# RF_Board_with_STM32.net
KiCad netlist of a schematic drawn in Altium Designer
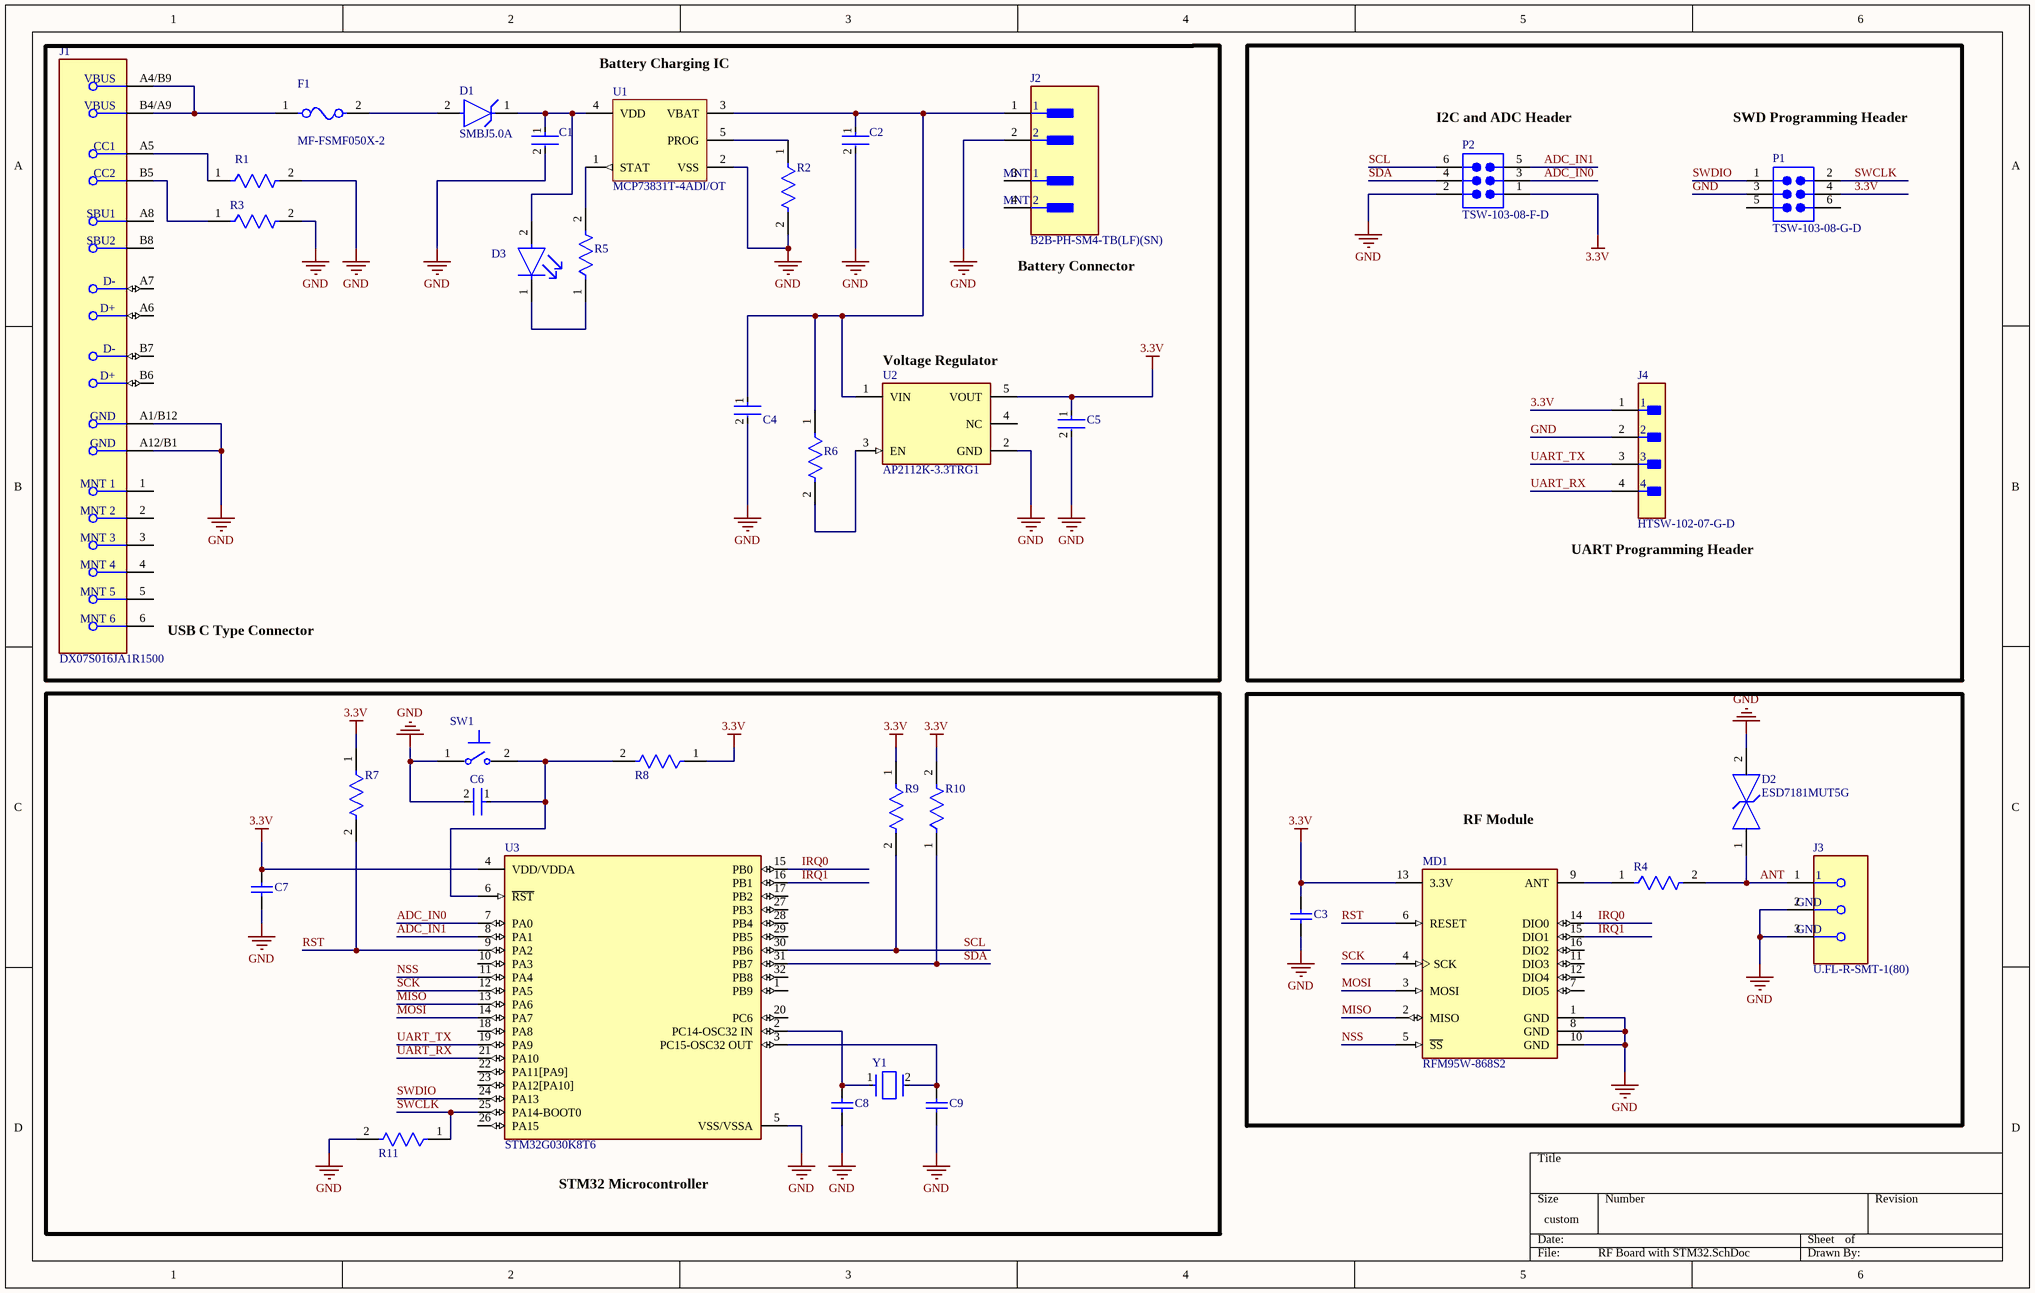
[diagram p0: RF Board with STM32.SchDoc]

(export (version "E")
  (design (tool "Eeschema 10.0.6"))
  (components
    (comp (ref "C1")
      (value "GRM188R61E475KE11J")
      (footprint "FP-GRM188-0_15-IPC_A")
      (description "Chip Multilayer Ceramic Capacitors for General Purpose, 0603, 4.7uF, X5R, 15%, 10%, 25V")
      (fields (field (name "TOLERANCE") "10%"))
      (libsource (lib "Altium Content Vault") (part "02cd4be3c70576c341d710602a673aa"))
    )
    (comp (ref "C2")
      (value "GRM188R61E475KE11J")
      (footprint "FP-GRM188-0_15-IPC_A")
      (description "Chip Multilayer Ceramic Capacitors for General Purpose, 0603, 4.7uF, X5R, 15%, 10%, 25V")
      (fields (field (name "TOLERANCE") "10%"))
      (libsource (lib "Altium Content Vault") (part "02cd4be3c70576c341d710602a673aa"))
    )
    (comp (ref "C3")
      (value "06031A100CAT2A")
      (footprint "CAPC1608X90X35ML15T15")
      (fields (field (name "MANUFACTURER") "AVX Interconnect / Elco"))
      (libsource (lib "Altium Content Vault") (part "CAP"))
    )
    (comp (ref "C4")
      (value "GRM155C81A105KA12J")
      (footprint "FP-GRM155-0_05-IPC_A")
      (description "Chip Multilayer Ceramic Capacitors for General Purpose, 0402, 1.0uF, X6S, 22%, 10%, 10V")
      (fields (field (name "TOLERANCE") "10%"))
      (libsource (lib "Altium Content Vault") (part "02cd4be3c70576c341d710602a673aa"))
    )
    (comp (ref "C5")
      (value "GRM155C81A105KA12J")
      (footprint "FP-GRM155-0_05-IPC_A")
      (description "Chip Multilayer Ceramic Capacitors for General Purpose, 0402, 1.0uF, X6S, 22%, 10%, 10V")
      (fields (field (name "TOLERANCE") "10%"))
      (libsource (lib "Altium Content Vault") (part "02cd4be3c70576c341d710602a673aa"))
    )
    (comp (ref "C6")
      (value "GRM033R61A104KE15D")
      (footprint "FP-GRM033-0_03-IPC_C")
      (description "Chip Multilayer Ceramic Capacitors for General Purpose, 0201, 0.10uF, X5R, 15%, 10%, 10V")
      (fields (field (name "TOLERANCE") "10%") (field (name "VOLTAGE") "10V"))
      (libsource (lib "Altium Content Vault") (part "b4654b650e69147ec39a6b967a45e02"))
    )
    (comp (ref "C7")
      (value "06031A100CAT2A")
      (footprint "CAPC1608X90X35ML15T15")
      (fields (field (name "MANUFACTURER") "AVX Interconnect / Elco"))
      (libsource (lib "Altium Content Vault") (part "CAP"))
    )
    (comp (ref "C8")
      (value "VJ0603Y104KXJAC")
      (footprint "CAPC1608X92X38NL15T08")
      (fields (field (name "MANUFACTURER") "Vitramon"))
      (libsource (lib "Altium Content Vault") (part "CAP"))
    )
    (comp (ref "C9")
      (value "VJ0603Y104KXJAC")
      (footprint "CAPC1608X92X38NL15T08")
      (fields (field (name "MANUFACTURER") "Vitramon"))
      (libsource (lib "Altium Content Vault") (part "CAP"))
    )
    (comp (ref "D1")
      (value "SMBJ5.0A")
      (footprint "FP-SMBJ-MFG")
      (description "TVS DIODE 5V 9.2V SMB")
      (fields
        (field (name "OCTOPART") "https://octopart.com/smbj5.0a-bourns-12809487")
        (field (name "MANUFACTURER") "Bourns Inc.")
      )
      (libsource (lib "Altium Content Vault") (part "f813f71cba58e380607f5dd3caf9714"))
    )
    (comp (ref "D2")
      (value "ESD7181MUT5G")
      (footprint "FP-152AF-MFG")
      (description "ESD7181MUT5G ESD Suppressor Diode TVS Bi-Dir 18.5V 2-Pin X3-DFN T/R / TVS DIODE 18.5VWM 35VC")
      (libsource (lib "Altium Content Vault") (part "11bd9d59d340f0612179daf16ad9b72"))
    )
    (comp (ref "D3")
      (value "LS R976-NR-1")
      (footprint "FP-LS_R976-MFG")
      (description "LED RED DIFFUSED 0805 SMD")
      (libsource (lib "Altium Content Vault") (part "8706943c75ba83719d021d2fdc84c58"))
    )
    (comp (ref "F1")
      (value "MF-FSMF050X-2")
      (footprint "FP-MF-FSMF-MFG")
      (description "PTC RESET FUSE 6V 500MA 0603")
      (fields
        (field (name "MANUFACTURER") "Bourns Inc.")
        (field (name "OCTOPART") "https://octopart.com/mf-fsmf050x-2-bourns-10470804")
      )
      (libsource (lib "Altium Content Vault") (part "5bcf9b9f640e542cf0359d10258e979"))
    )
    (comp (ref "J1")
      (value "DX07S016JA1R1500")
      (footprint "FP-DX07S016JA1R1500-MFG")
      (description "CONN RCP USB2.0 TYP C 24P SMD RA")
      (libsource (lib "Altium Content Vault") (part "7f3e9989102a0f22bff9cb010881d34"))
    )
    (comp (ref "J2")
      (value "B2B-PH-SM4-TB(LF)(SN)")
      (footprint "FP-B2B-PH-SM4-TB_LF_SN-MFG")
      (description "CONN HEADER SMD 2POS 2MM")
      (libsource (lib "Altium Content Vault") (part "56ec3178a87b3978bdc1b3682cd516a"))
    )
    (comp (ref "J3")
      (value "U.FL-R-SMT-1(80)")
      (footprint "FP-U_FL-R-SMT-1_80-MFG")
      (description "CONN U.FL RCPT STR 50 OHM SMD")
      (libsource (lib "Altium Content Vault") (part "ad010367dc7cd7c7a13299a56582dd6"))
    )
    (comp (ref "J4")
      (value "HTSW-102-07-G-D")
      (footprint "FP-HTSW-102-07-G-D-MFG")
      (description "CONN HEADER VERT 4POS 2.54MM")
      (fields
        (field (name "MANUFACTURER") "Samtec")
        (field (name "OCTOPART") "https://octopart.com/htsw-102-07-g-d-samtec-10531767")
      )
      (libsource (lib "Altium Content Vault") (part "299a8cea1bdcbc3624fe62c390fa72c"))
    )
    (comp (ref "MD1")
      (value "RFM95W-868S2")
      (footprint "FP-RFM95W-868S2-MFG")
      (description "RX TXRX MODULE ISM < 1GHZ SMD")
      (libsource (lib "Altium Content Vault") (part "17626aa6fba47fab2b206b7c140802e"))
    )
    (comp (ref "P1")
      (value "TSW-103-08-G-D")
      (footprint "SMTC-TSW-103-08-X-D")
      (description "0.025\" SQ Post Header, Through-hole, Vertical, -55 to 125 degC, 2.54 mm Pitch, 6-Pin, Male, RoHS")
      (fields (field (name "MANUFACTURER") "Samtec"))
      (libsource (lib "Altium Content Vault") (part "SMTC-TSW-103-08-X-D"))
    )
    (comp (ref "P2")
      (value "TSW-103-08-F-D")
      (footprint "SMTC-TSW-103-08-X-D")
      (description "0.025\" SQ Post Header, Through-hole, Vertical, -55 to 125 degC, 2.54 mm Pitch, 6-Pin, Male, RoHS")
      (fields (field (name "MANUFACTURER") "Samtec"))
      (libsource (lib "Altium Content Vault") (part "SMTC-TSW-103-08-X-D"))
    )
    (comp (ref "R1")
      (value "AC0603FR-075K1L")
      (footprint "FP-AC0603-MFG")
      (description "RES 5.1KΩ 1.00% 0.1W 0603")
      (fields (field (name "TOLERANCE") "1%"))
      (libsource (lib "Altium Content Vault") (part "1029c3af85768c4190bb7ad29bc67b5"))
    )
    (comp (ref "R2")
      (value "RP73PF1J2K0BTDF")
      (footprint "FP-RP73P-1J-MFG")
      (description "RES SMD 2K OHM 0.1% 1/6W 0603")
      (fields (field (name "TOLERANCE") "0.001") (field (name "MANUFACTURER") "TE Connectivity"))
      (libsource (lib "Altium Content Vault") (part "1029c3af85768c4190bb7ad29bc67b5"))
    )
    (comp (ref "R3")
      (value "AC0603FR-075K1L")
      (footprint "FP-AC0603-MFG")
      (description "RES 5.1KΩ 1.00% 0.1W 0603")
      (fields (field (name "TOLERANCE") "1%"))
      (libsource (lib "Altium Content Vault") (part "1029c3af85768c4190bb7ad29bc67b5"))
    )
    (comp (ref "R4")
      (value "CRG0603ZR")
      (footprint "FP-CRG0603-IPC_C")
      (description "RES SMD 0 OHM JUMPER 1/10W 0603")
      (fields (field (name "TOLERANCE") "0%"))
      (libsource (lib "Altium Content Vault") (part "1029c3af85768c4190bb7ad29bc67b5"))
    )
    (comp (ref "R5")
      (value "RT0603BRD07470RL")
      (footprint "FP-RT0603-MFG")
      (description "RES SMD 470 OHM 0.1% 1/10W 0603")
      (fields
        (field (name "OCTOPART") "https://octopart.com/rt0603brd07470rl-yageo-1424253")
        (field (name "MANUFACTURER") "Yageo")
      )
      (libsource (lib "Altium Content Vault") (part "1029c3af85768c4190bb7ad29bc67b5"))
    )
    (comp (ref "R6")
      (value "ERJ-U02F1003X")
      (footprint "FP-ERJU02-MFG")
      (fields (field (name "TOLERANCE") "1%"))
      (libsource (lib "Altium Content Vault") (part "1029c3af85768c4190bb7ad29bc67b5"))
    )
    (comp (ref "R7")
      (value "RT0603FRE1010KL")
      (footprint "FP-RT0603-MFG")
      (description "RT0603 10KΩ 0.1W 50 ppm/°C 1.00%")
      (fields
        (field (name "OCTOPART") "https://octopart.com/rt0603fre1010kl-yageo-26185585")
        (field (name "TOLERANCE") "0.01")
      )
      (libsource (lib "Altium Content Vault") (part "1029c3af85768c4190bb7ad29bc67b5"))
    )
    (comp (ref "R8")
      (value "RT0603FRE1010KL")
      (footprint "FP-RT0603-MFG")
      (description "RT0603 10KΩ 0.1W 50 ppm/°C 1.00%")
      (fields
        (field (name "OCTOPART") "https://octopart.com/rt0603fre1010kl-yageo-26185585")
        (field (name "TOLERANCE") "0.01")
      )
      (libsource (lib "Altium Content Vault") (part "1029c3af85768c4190bb7ad29bc67b5"))
    )
    (comp (ref "R9")
      (value "CRG0402F4K7")
      (footprint "FP-CRG0402-IPC_B")
      (description "RES SMD 4.7K OHM 1% 1/16W 0402")
      (libsource (lib "Altium Content Vault") (part "1029c3af85768c4190bb7ad29bc67b5"))
    )
    (comp (ref "R10")
      (value "CRG0402F4K7")
      (footprint "FP-CRG0402-IPC_B")
      (description "RES SMD 4.7K OHM 1% 1/16W 0402")
      (libsource (lib "Altium Content Vault") (part "1029c3af85768c4190bb7ad29bc67b5"))
    )
    (comp (ref "R11")
      (value "RT0603FRE1010KL")
      (footprint "FP-RT0603-MFG")
      (description "RT0603 10KΩ 0.1W 50 ppm/°C 1.00%")
      (fields
        (field (name "OCTOPART") "https://octopart.com/rt0603fre1010kl-yageo-26185585")
        (field (name "TOLERANCE") "0.01")
      )
      (libsource (lib "Altium Content Vault") (part "1029c3af85768c4190bb7ad29bc67b5"))
    )
    (comp (ref "SW1")
      (value "TL1015AF160QG")
      (footprint "FP-TL1015AF160QG-MFG")
      (description "SWITCH TACTILE SPST-NO 0.05A 12V")
      (libsource (lib "Altium Content Vault") (part "2041f8efb62e6aaa548c9fd35e2c2f1"))
    )
    (comp (ref "U1")
      (value "MCP73831T-4ADI/OT")
      (footprint "SOT-23-OT5_N")
      (libsource (lib "Altium Content Vault") (part "PM-BM-MCP73831-SOT5"))
    )
    (comp (ref "U2")
      (value "AP2112K-3.3TRG1")
      (footprint "FP-SOT25-IPC_A")
      (description "IC REG LINEAR 3.3V 600MA SOT25")
      (libsource (lib "Altium Content Vault") (part "c8ab751aee5229183125ab046a11caa"))
    )
    (comp (ref "U3")
      (value "STM32G030K8T6")
      (footprint "FP-LQFP32-5V-IPC_A")
      (description "IC MCU 32BIT 64KB FLASH 32LQFP")
      (libsource (lib "Altium Content Vault") (part "fea91388a178aa646681c81fcef9c35"))
    )
    (comp (ref "Y1")
      (value "ABS07-32.768KHZ-7-T")
      (footprint "FP-ABS07-MFG")
      (description "Crystal 32.768kHz ±20ppm (Tol) 7pF FUND 70kΩ 2-Pin CSMD T/R")
      (fields (field (name "TOLERANCE") "20ppm"))
      (libsource (lib "Altium Content Vault") (part "c23a69dc6c9e2f18f2079038eb95dd1"))
    )
  )
  (nets
    (net (code "2") (name "/ADC_IN0") (class "Default")
      (node (ref "P2") (pin "3") (pinfunction "3_3") (pintype "passive"))
      (node (ref "U3") (pin "7") (pinfunction "PA0_7") (pintype "bidirectional"))
    )
    (net (code "3") (name "/ADC_IN1") (class "Default")
      (node (ref "P2") (pin "5") (pinfunction "5_5") (pintype "passive"))
      (node (ref "U3") (pin "8") (pinfunction "PA1_8") (pintype "bidirectional"))
    )
    (net (code "4") (name "/ANT") (class "Default")
      (node (ref "D2") (pin "1") (pinfunction "1_1") (pintype "passive"))
      (node (ref "J3") (pin "1") (pinfunction "1_1") (pintype "passive"))
      (node (ref "R4") (pin "2") (pinfunction "2_2") (pintype "passive"))
    )
    (net (code "5") (name "/IRQ0") (class "Default")
      (node (ref "MD1") (pin "14") (pinfunction "DIO0_14") (pintype "bidirectional"))
      (node (ref "U3") (pin "15") (pinfunction "PB0_15") (pintype "bidirectional"))
    )
    (net (code "6") (name "/IRQ1") (class "Default")
      (node (ref "MD1") (pin "15") (pinfunction "DIO1_15") (pintype "bidirectional"))
      (node (ref "U3") (pin "16") (pinfunction "PB1_16") (pintype "bidirectional"))
    )
    (net (code "7") (name "/MISO") (class "Default")
      (node (ref "MD1") (pin "2") (pinfunction "MISO_2") (pintype "bidirectional"))
      (node (ref "U3") (pin "13") (pinfunction "PA6_13") (pintype "bidirectional"))
    )
    (net (code "8") (name "/MOSI") (class "Default")
      (node (ref "MD1") (pin "3") (pinfunction "MOSI_3") (pintype "input"))
      (node (ref "U3") (pin "14") (pinfunction "PA7_14") (pintype "bidirectional"))
    )
    (net (code "9") (name "/NSS") (class "Default")
      (node (ref "MD1") (pin "5") (pinfunction "~{SS}_5") (pintype "input"))
      (node (ref "U3") (pin "11") (pinfunction "PA4_11") (pintype "bidirectional"))
    )
    (net (code "10") (name "/RST") (class "Default")
      (node (ref "MD1") (pin "6") (pinfunction "RESET_6") (pintype "input"))
      (node (ref "R7") (pin "2") (pinfunction "2_2") (pintype "passive"))
      (node (ref "U3") (pin "9") (pinfunction "PA2_9") (pintype "bidirectional"))
    )
    (net (code "11") (name "/SCK") (class "Default")
      (node (ref "MD1") (pin "4") (pinfunction "SCK_4") (pintype "input"))
      (node (ref "U3") (pin "12") (pinfunction "PA5_12") (pintype "bidirectional"))
    )
    (net (code "12") (name "/SCL") (class "Default")
      (node (ref "P2") (pin "6") (pinfunction "6_6") (pintype "passive"))
      (node (ref "R9") (pin "2") (pinfunction "2_2") (pintype "passive"))
      (node (ref "U3") (pin "30") (pinfunction "PB6_30") (pintype "bidirectional"))
    )
    (net (code "13") (name "/SDA") (class "Default")
      (node (ref "P2") (pin "4") (pinfunction "4_4") (pintype "passive"))
      (node (ref "R10") (pin "1") (pinfunction "1_1") (pintype "passive"))
      (node (ref "U3") (pin "31") (pinfunction "PB7_31") (pintype "bidirectional"))
    )
    (net (code "14") (name "/SWCLK") (class "Default")
      (node (ref "P1") (pin "2") (pinfunction "2_2") (pintype "passive"))
      (node (ref "R11") (pin "1") (pinfunction "1_1") (pintype "passive"))
      (node (ref "U3") (pin "25") (pinfunction "PA14-BOOT0_25") (pintype "bidirectional"))
    )
    (net (code "15") (name "/SWDIO") (class "Default")
      (node (ref "P1") (pin "1") (pinfunction "1_1") (pintype "passive"))
      (node (ref "U3") (pin "24") (pinfunction "PA13_24") (pintype "bidirectional"))
    )
    (net (code "16") (name "/UART_RX") (class "Default")
      (node (ref "J4") (pin "4") (pinfunction "4_4") (pintype "passive"))
      (node (ref "U3") (pin "21") (pinfunction "PA10_21") (pintype "bidirectional"))
    )
    (net (code "17") (name "/UART_TX") (class "Default")
      (node (ref "J4") (pin "3") (pinfunction "3_3") (pintype "passive"))
      (node (ref "U3") (pin "19") (pinfunction "PA9_19") (pintype "bidirectional"))
    )
    (net (code "18") (name "3.3V") (class "Default")
      (node (ref "C3") (pin "2") (pinfunction "2_2") (pintype "passive"))
      (node (ref "C5") (pin "1") (pinfunction "1_1") (pintype "passive"))
      (node (ref "C7") (pin "2") (pinfunction "2_2") (pintype "passive"))
      (node (ref "J4") (pin "1") (pinfunction "1_1") (pintype "passive"))
      (node (ref "MD1") (pin "13") (pinfunction "3.3V_13") (pintype "power_in"))
      (node (ref "P1") (pin "4") (pinfunction "4_4") (pintype "passive"))
      (node (ref "P2") (pin "1") (pinfunction "1_1") (pintype "passive"))
      (node (ref "R10") (pin "2") (pinfunction "2_2") (pintype "passive"))
      (node (ref "R7") (pin "1") (pinfunction "1_1") (pintype "passive"))
      (node (ref "R8") (pin "1") (pinfunction "1_1") (pintype "passive"))
      (node (ref "R9") (pin "1") (pinfunction "1_1") (pintype "passive"))
      (node (ref "U2") (pin "5") (pinfunction "VOUT_5") (pintype "power_in"))
      (node (ref "U3") (pin "4") (pinfunction "VDD/VDDA_4") (pintype "power_in"))
    )
    (net (code "19") (name "GND") (class "Default")
      (node (ref "C1") (pin "2") (pinfunction "2_2") (pintype "passive"))
      (node (ref "C2") (pin "2") (pinfunction "2_2") (pintype "passive"))
      (node (ref "C3") (pin "1") (pinfunction "1_1") (pintype "passive"))
      (node (ref "C4") (pin "2") (pinfunction "2_2") (pintype "passive"))
      (node (ref "C5") (pin "2") (pinfunction "2_2") (pintype "passive"))
      (node (ref "C6") (pin "2") (pinfunction "2_2") (pintype "passive"))
      (node (ref "C7") (pin "1") (pinfunction "1_1") (pintype "passive"))
      (node (ref "C8") (pin "1") (pinfunction "1_1") (pintype "passive"))
      (node (ref "C9") (pin "1") (pinfunction "1_1") (pintype "passive"))
      (node (ref "D2") (pin "2") (pinfunction "2_2") (pintype "passive"))
      (node (ref "J1") (pin "A1/B12") (pinfunction "GND_A1/B12") (pintype "power_in"))
      (node (ref "J1") (pin "A12/B1") (pinfunction "GND_A12/B1") (pintype "power_in"))
      (node (ref "J2") (pin "2") (pinfunction "2_2") (pintype "passive"))
      (node (ref "J3") (pin "2") (pinfunction "GND_2") (pintype "power_in"))
      (node (ref "J3") (pin "3") (pinfunction "GND_3") (pintype "power_in"))
      (node (ref "J4") (pin "2") (pinfunction "2_2") (pintype "passive"))
      (node (ref "MD1") (pin "1") (pinfunction "GND_1") (pintype "power_in"))
      (node (ref "MD1") (pin "10") (pinfunction "GND_10") (pintype "power_in"))
      (node (ref "MD1") (pin "8") (pinfunction "GND_8") (pintype "power_in"))
      (node (ref "P1") (pin "3") (pinfunction "3_3") (pintype "passive"))
      (node (ref "P2") (pin "2") (pinfunction "2_2") (pintype "passive"))
      (node (ref "R1") (pin "2") (pinfunction "2_2") (pintype "passive"))
      (node (ref "R11") (pin "2") (pinfunction "2_2") (pintype "passive"))
      (node (ref "R2") (pin "2") (pinfunction "2_2") (pintype "passive"))
      (node (ref "R3") (pin "2") (pinfunction "2_2") (pintype "passive"))
      (node (ref "SW1") (pin "1") (pinfunction "1_1") (pintype "passive"))
      (node (ref "U1") (pin "2") (pinfunction "VSS_2") (pintype "power_in"))
      (node (ref "U2") (pin "2") (pinfunction "GND_2") (pintype "power_in"))
      (node (ref "U3") (pin "5") (pinfunction "VSS/VSSA_5") (pintype "power_in"))
    )
    (net (code "20") (name "Net-(D1-A)") (class "Default")
      (node (ref "D1") (pin "2") (pinfunction "A_2") (pintype "passive"))
      (node (ref "F1") (pin "2") (pinfunction "2_2") (pintype "passive"))
    )
    (net (code "21") (name "Net-(D1-C)") (class "Default")
      (node (ref "C1") (pin "1") (pinfunction "1_1") (pintype "passive"))
      (node (ref "D1") (pin "1") (pinfunction "C_1") (pintype "passive"))
      (node (ref "D3") (pin "2") (pinfunction "A_2") (pintype "passive"))
      (node (ref "U1") (pin "4") (pinfunction "VDD_4") (pintype "power_in"))
    )
    (net (code "22") (name "Net-(D3-C)") (class "Default")
      (node (ref "D3") (pin "1") (pinfunction "C_1") (pintype "passive"))
      (node (ref "R5") (pin "1") (pinfunction "1_1") (pintype "passive"))
    )
    (net (code "23") (name "Net-(F1-Pad1)") (class "Default")
      (node (ref "F1") (pin "1") (pinfunction "1_1") (pintype "passive"))
      (node (ref "J1") (pin "A4/B9") (pinfunction "VBUS_A4/B9") (pintype "power_in"))
      (node (ref "J1") (pin "B4/A9") (pinfunction "VBUS_B4/A9") (pintype "power_in"))
    )
    (net (code "24") (name "Net-(J1-CC1)") (class "Default")
      (node (ref "J1") (pin "A5") (pinfunction "CC1_A5") (pintype "passive"))
      (node (ref "R1") (pin "1") (pinfunction "1_1") (pintype "passive"))
    )
    (net (code "25") (name "Net-(J1-CC2)") (class "Default")
      (node (ref "J1") (pin "B5") (pinfunction "CC2_B5") (pintype "passive"))
      (node (ref "R3") (pin "1") (pinfunction "1_1") (pintype "passive"))
    )
    (net (code "26") (name "Net-(MD1-ANT)") (class "Default")
      (node (ref "MD1") (pin "9") (pinfunction "ANT_9") (pintype "passive"))
      (node (ref "R4") (pin "1") (pinfunction "1_1") (pintype "passive"))
    )
    (net (code "27") (name "Net-(U1-PROG)") (class "Default")
      (node (ref "R2") (pin "1") (pinfunction "1_1") (pintype "passive"))
      (node (ref "U1") (pin "5") (pinfunction "PROG_5") (pintype "passive"))
    )
    (net (code "28") (name "Net-(U1-STAT)") (class "Default")
      (node (ref "R5") (pin "2") (pinfunction "2_2") (pintype "passive"))
      (node (ref "U1") (pin "1") (pinfunction "STAT_1") (pintype "output"))
    )
    (net (code "29") (name "Net-(U1-VBAT)") (class "Default")
      (node (ref "C2") (pin "1") (pinfunction "1_1") (pintype "passive"))
      (node (ref "C4") (pin "1") (pinfunction "1_1") (pintype "passive"))
      (node (ref "J2") (pin "1") (pinfunction "1_1") (pintype "passive"))
      (node (ref "R6") (pin "1") (pinfunction "1_1") (pintype "passive"))
      (node (ref "U1") (pin "3") (pinfunction "VBAT_3") (pintype "power_in"))
      (node (ref "U2") (pin "1") (pinfunction "VIN_1") (pintype "power_in"))
    )
    (net (code "30") (name "Net-(U2-EN)") (class "Default")
      (node (ref "R6") (pin "2") (pinfunction "2_2") (pintype "passive"))
      (node (ref "U2") (pin "3") (pinfunction "EN_3") (pintype "input"))
    )
    (net (code "31") (name "Net-(U3-PC14-OSC32_IN)") (class "Default")
      (node (ref "C8") (pin "2") (pinfunction "2_2") (pintype "passive"))
      (node (ref "U3") (pin "2") (pinfunction "PC14-OSC32_IN_2") (pintype "bidirectional"))
      (node (ref "Y1") (pin "1") (pinfunction "1_1") (pintype "passive"))
    )
    (net (code "32") (name "Net-(U3-PC15-OSC32_OUT)") (class "Default")
      (node (ref "C9") (pin "2") (pinfunction "2_2") (pintype "passive"))
      (node (ref "U3") (pin "3") (pinfunction "PC15-OSC32_OUT_3") (pintype "bidirectional"))
      (node (ref "Y1") (pin "2") (pinfunction "2_2") (pintype "passive"))
    )
    (net (code "33") (name "Net-(U3-~{RST})") (class "Default")
      (node (ref "C6") (pin "1") (pinfunction "1_1") (pintype "passive"))
      (node (ref "R8") (pin "2") (pinfunction "2_2") (pintype "passive"))
      (node (ref "SW1") (pin "2") (pinfunction "2_2") (pintype "passive"))
      (node (ref "U3") (pin "6") (pinfunction "~{RST}_6") (pintype "input"))
    )
    (net (code "34") (name "unconnected-(J1-D+-PadA6)") (class "Default")
      (node (ref "J1") (pin "A6") (pinfunction "D+_A6") (pintype "bidirectional"))
    )
    (net (code "35") (name "unconnected-(J1-D+-PadB6)") (class "Default")
      (node (ref "J1") (pin "B6") (pinfunction "D+_B6") (pintype "bidirectional"))
    )
    (net (code "36") (name "unconnected-(J1-D--PadA7)") (class "Default")
      (node (ref "J1") (pin "A7") (pinfunction "D-_A7") (pintype "bidirectional"))
    )
    (net (code "37") (name "unconnected-(J1-D--PadB7)") (class "Default")
      (node (ref "J1") (pin "B7") (pinfunction "D-_B7") (pintype "bidirectional"))
    )
    (net (code "38") (name "unconnected-(J1-MNT_1-Pad1)") (class "Default")
      (node (ref "J1") (pin "1") (pinfunction "MNT_1_1") (pintype "passive"))
    )
    (net (code "39") (name "unconnected-(J1-MNT_2-Pad2)") (class "Default")
      (node (ref "J1") (pin "2") (pinfunction "MNT_2_2") (pintype "passive"))
    )
    (net (code "40") (name "unconnected-(J1-MNT_3-Pad3)") (class "Default")
      (node (ref "J1") (pin "3") (pinfunction "MNT_3_3") (pintype "passive"))
    )
    (net (code "41") (name "unconnected-(J1-MNT_4-Pad4)") (class "Default")
      (node (ref "J1") (pin "4") (pinfunction "MNT_4_4") (pintype "passive"))
    )
    (net (code "42") (name "unconnected-(J1-MNT_5-Pad5)") (class "Default")
      (node (ref "J1") (pin "5") (pinfunction "MNT_5_5") (pintype "passive"))
    )
    (net (code "43") (name "unconnected-(J1-MNT_6-Pad6)") (class "Default")
      (node (ref "J1") (pin "6") (pinfunction "MNT_6_6") (pintype "passive"))
    )
    (net (code "44") (name "unconnected-(J1-SBU1-PadA8)") (class "Default")
      (node (ref "J1") (pin "A8") (pinfunction "SBU1_A8") (pintype "passive"))
    )
    (net (code "45") (name "unconnected-(J1-SBU2-PadB8)") (class "Default")
      (node (ref "J1") (pin "B8") (pinfunction "SBU2_B8") (pintype "passive"))
    )
    (net (code "46") (name "unconnected-(J2-MNT_1-Pad3)") (class "Default")
      (node (ref "J2") (pin "3") (pinfunction "MNT_1_3") (pintype "passive"))
    )
    (net (code "47") (name "unconnected-(J2-MNT_2-Pad4)") (class "Default")
      (node (ref "J2") (pin "4") (pinfunction "MNT_2_4") (pintype "passive"))
    )
    (net (code "48") (name "unconnected-(MD1-DIO2-Pad16)") (class "Default")
      (node (ref "MD1") (pin "16") (pinfunction "DIO2_16") (pintype "bidirectional"))
    )
    (net (code "49") (name "unconnected-(MD1-DIO3-Pad11)") (class "Default")
      (node (ref "MD1") (pin "11") (pinfunction "DIO3_11") (pintype "bidirectional"))
    )
    (net (code "50") (name "unconnected-(MD1-DIO4-Pad12)") (class "Default")
      (node (ref "MD1") (pin "12") (pinfunction "DIO4_12") (pintype "bidirectional"))
    )
    (net (code "51") (name "unconnected-(MD1-DIO5-Pad7)") (class "Default")
      (node (ref "MD1") (pin "7") (pinfunction "DIO5_7") (pintype "bidirectional"))
    )
    (net (code "52") (name "unconnected-(P1-Pad5)") (class "Default")
      (node (ref "P1") (pin "5") (pinfunction "5_5") (pintype "passive"))
    )
    (net (code "53") (name "unconnected-(P1-Pad6)") (class "Default")
      (node (ref "P1") (pin "6") (pinfunction "6_6") (pintype "passive"))
    )
    (net (code "54") (name "unconnected-(U2-NC-Pad4)") (class "Default")
      (node (ref "U2") (pin "4") (pinfunction "NC_4") (pintype "passive"))
    )
    (net (code "55") (name "unconnected-(U3-PA3-Pad10)") (class "Default")
      (node (ref "U3") (pin "10") (pinfunction "PA3_10") (pintype "bidirectional"))
    )
    (net (code "56") (name "unconnected-(U3-PA8-Pad18)") (class "Default")
      (node (ref "U3") (pin "18") (pinfunction "PA8_18") (pintype "bidirectional"))
    )
    (net (code "57") (name "unconnected-(U3-PA11[PA9]-Pad22)") (class "Default")
      (node (ref "U3") (pin "22") (pinfunction "PA11[PA9]_22") (pintype "bidirectional"))
    )
    (net (code "58") (name "unconnected-(U3-PA12[PA10]-Pad23)") (class "Default")
      (node (ref "U3") (pin "23") (pinfunction "PA12[PA10]_23") (pintype "bidirectional"))
    )
    (net (code "59") (name "unconnected-(U3-PA15-Pad26)") (class "Default")
      (node (ref "U3") (pin "26") (pinfunction "PA15_26") (pintype "bidirectional"))
    )
    (net (code "60") (name "unconnected-(U3-PB2-Pad17)") (class "Default")
      (node (ref "U3") (pin "17") (pinfunction "PB2_17") (pintype "bidirectional"))
    )
    (net (code "61") (name "unconnected-(U3-PB3-Pad27)") (class "Default")
      (node (ref "U3") (pin "27") (pinfunction "PB3_27") (pintype "bidirectional"))
    )
    (net (code "62") (name "unconnected-(U3-PB4-Pad28)") (class "Default")
      (node (ref "U3") (pin "28") (pinfunction "PB4_28") (pintype "bidirectional"))
    )
    (net (code "63") (name "unconnected-(U3-PB5-Pad29)") (class "Default")
      (node (ref "U3") (pin "29") (pinfunction "PB5_29") (pintype "bidirectional"))
    )
    (net (code "64") (name "unconnected-(U3-PB8-Pad32)") (class "Default")
      (node (ref "U3") (pin "32") (pinfunction "PB8_32") (pintype "bidirectional"))
    )
    (net (code "65") (name "unconnected-(U3-PB9-Pad1)") (class "Default")
      (node (ref "U3") (pin "1") (pinfunction "PB9_1") (pintype "bidirectional"))
    )
    (net (code "66") (name "unconnected-(U3-PC6-Pad20)") (class "Default")
      (node (ref "U3") (pin "20") (pinfunction "PC6_20") (pintype "bidirectional"))
    )
  )
)
